# BleAx_nRF52832.net
KiCad netlist of a schematic drawn in EAGLE
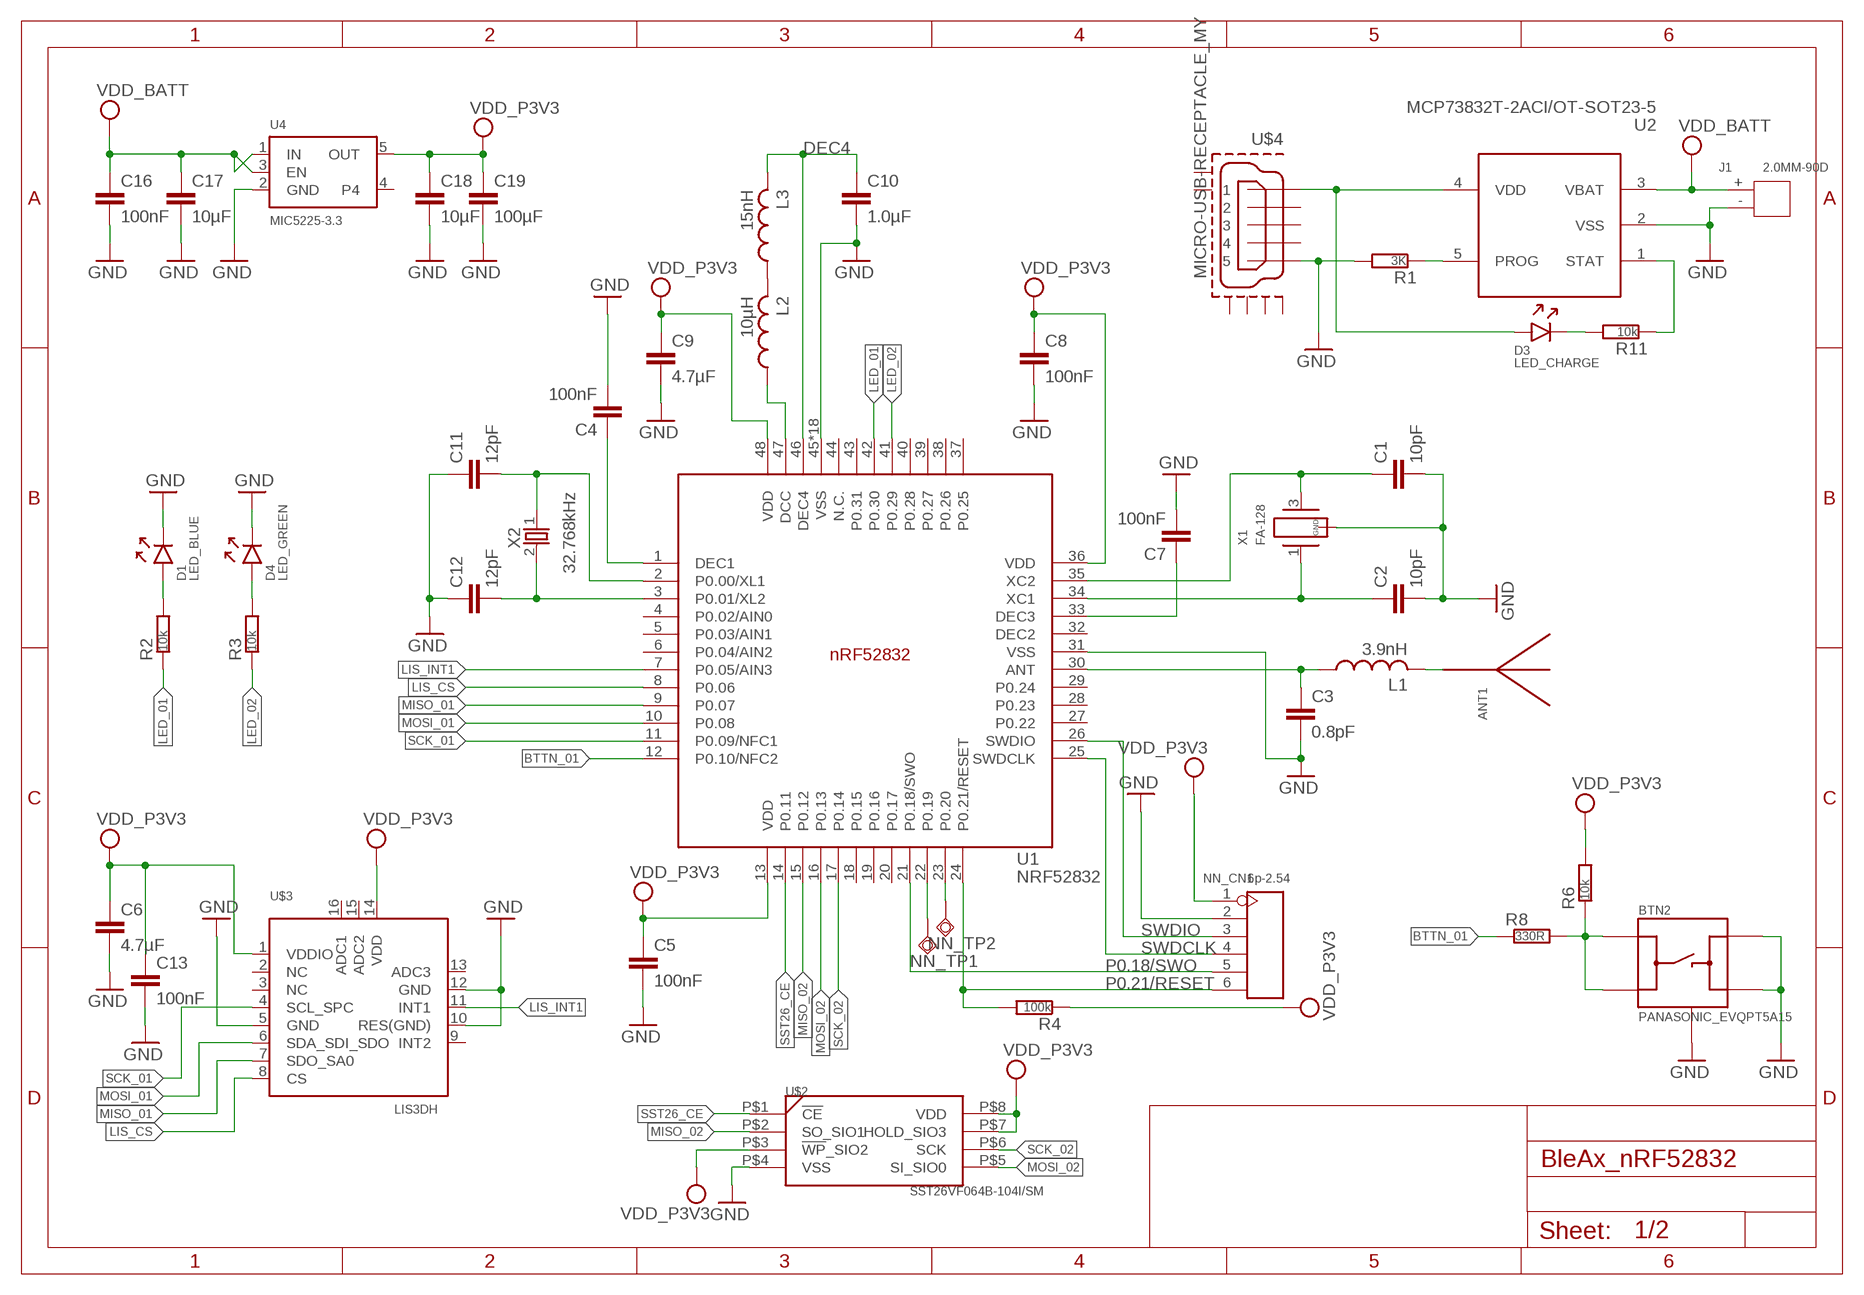
[diagram p0: schematic, sheet 1]
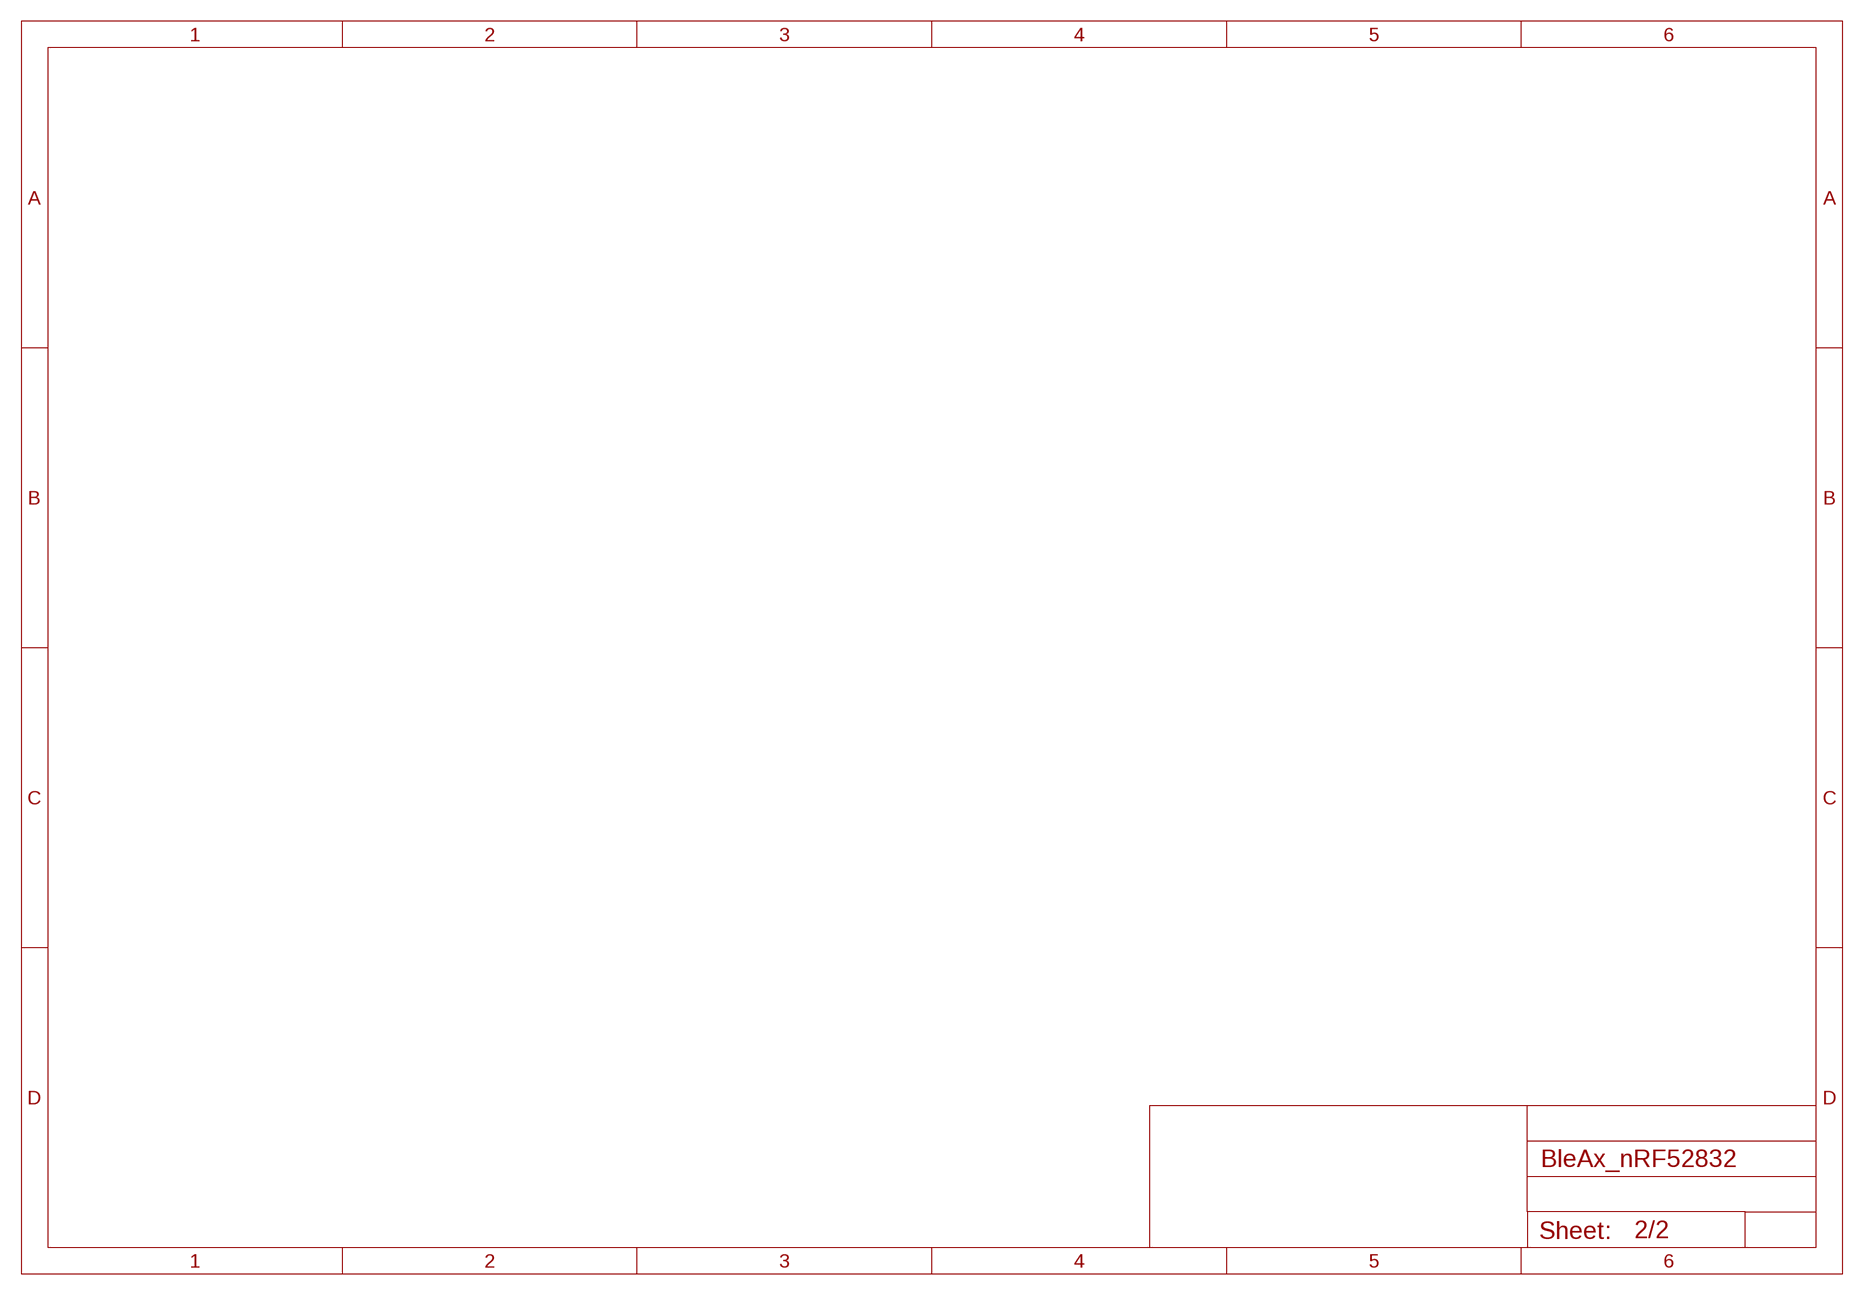
[diagram p1: schematic, sheet 2]

(export (version "E")
  (design (tool "Eeschema 10.0.6"))
  (components
    (comp (ref "ANT1")
      (value "ANTENNA_QUARTER-WAVE_MONOPOLE_MEANDERED_LEFT")
      (footprint "eagle-import:QWMP_MEANDERED_LEFT_+6")
      (libsource (lib "eagle-import") (part "ANTENNA_QUARTER-WAVE_MONOPOLE_MEANDERED_LEFT"))
    )
    (comp (ref "BTN2")
      (value "PANASONIC_EVQPT5A15")
      (footprint "eagle-import:PANASONIC_EVQPT5A15")
      (libsource (lib "eagle-import") (part "PANASONIC_EVQPT5A15"))
    )
    (comp (ref "C1")
      (value "10pF")
      (footprint "eagle-import:RESC0402_N")
      (libsource (lib "eagle-import") (part "CAPACITOR_0402_N"))
    )
    (comp (ref "C2")
      (value "10pF")
      (footprint "eagle-import:RESC0402_N")
      (libsource (lib "eagle-import") (part "CAPACITOR_0402_N"))
    )
    (comp (ref "C3")
      (value "0.8pF")
      (footprint "eagle-import:RESC0402_N")
      (libsource (lib "eagle-import") (part "CAPACITOR_0402_N"))
    )
    (comp (ref "C4")
      (value "100nF")
      (footprint "eagle-import:RESC0402_N")
      (libsource (lib "eagle-import") (part "CAPACITOR_0402_N"))
    )
    (comp (ref "C5")
      (value "100nF")
      (footprint "eagle-import:RESC0402_N")
      (libsource (lib "eagle-import") (part "CAPACITOR_0402_N"))
    )
    (comp (ref "C6")
      (value "4.7µF")
      (footprint "eagle-import:RESC0603_N")
      (libsource (lib "eagle-import") (part "CAPACITOR_0603_N"))
    )
    (comp (ref "C7")
      (value "100nF")
      (footprint "eagle-import:RESC0402_N")
      (libsource (lib "eagle-import") (part "CAPACITOR_0402_N"))
    )
    (comp (ref "C8")
      (value "100nF")
      (footprint "eagle-import:RESC0402_N")
      (libsource (lib "eagle-import") (part "CAPACITOR_0402_N"))
    )
    (comp (ref "C9")
      (value "4.7µF")
      (footprint "eagle-import:RESC0603_N")
      (libsource (lib "eagle-import") (part "CAPACITOR_0603_N"))
    )
    (comp (ref "C10")
      (value "1.0µF")
      (footprint "eagle-import:RESC0603_N")
      (libsource (lib "eagle-import") (part "CAPACITOR_0603_N"))
    )
    (comp (ref "C11")
      (value "12pF")
      (footprint "eagle-import:RESC0402_N")
      (libsource (lib "eagle-import") (part "CAPACITOR_0402_N"))
    )
    (comp (ref "C12")
      (value "12pF")
      (footprint "eagle-import:RESC0402_N")
      (libsource (lib "eagle-import") (part "CAPACITOR_0402_N"))
    )
    (comp (ref "C13")
      (value "100nF")
      (footprint "eagle-import:RESC0402_N")
      (libsource (lib "eagle-import") (part "CAPACITOR_0402_N"))
    )
    (comp (ref "C16")
      (value "100nF")
      (footprint "eagle-import:RESC0402_N")
      (libsource (lib "eagle-import") (part "CAPACITOR_0402_N"))
    )
    (comp (ref "C17")
      (value "10µF")
      (footprint "eagle-import:RESC0603_N")
      (libsource (lib "eagle-import") (part "CAPACITOR_0603_N"))
    )
    (comp (ref "C18")
      (value "10µF")
      (footprint "eagle-import:RESC0603_N")
      (libsource (lib "eagle-import") (part "CAPACITOR_0603_N"))
    )
    (comp (ref "C19")
      (value "100µF")
      (footprint "eagle-import:RESC0805_N")
      (libsource (lib "eagle-import") (part "CAPACITOR_0805_N"))
    )
    (comp (ref "D1")
      (value "LED_BLUE")
      (footprint "eagle-import:DIOC0603_N")
      (libsource (lib "eagle-import") (part "LED"))
    )
    (comp (ref "D3")
      (value "LED_CHARGE")
      (footprint "eagle-import:DIOC0603_N")
      (libsource (lib "eagle-import") (part "LED"))
    )
    (comp (ref "D4")
      (value "LED_GREEN")
      (footprint "eagle-import:DIOC0603_N")
      (libsource (lib "eagle-import") (part "LED"))
    )
    (comp (ref "J1")
      (value "2.0MM-90D")
      (footprint "eagle-import:H2-2.0-90D")
      (libsource (lib "eagle-import") (part "CONN-HEADER-PH-SIDE-(2P-2.0MM)'90D'"))
    )
    (comp (ref "L1")
      (value "3.9nH")
      (footprint "eagle-import:RESC0402_N")
      (libsource (lib "eagle-import") (part "INDUCTOR_0402_N"))
    )
    (comp (ref "L2")
      (value "10µH")
      (footprint "eagle-import:RESC0603_N")
      (libsource (lib "eagle-import") (part "INDUCTOR_0603_N"))
    )
    (comp (ref "L3")
      (value "15nH")
      (footprint "eagle-import:RESC0402_N")
      (libsource (lib "eagle-import") (part "INDUCTOR_0402_N"))
    )
    (comp (ref "NN_CN1")
      (value "6p-2.54")
      (footprint "eagle-import:H6-2.54")
      (fields (field (name "MPN") "F185-1106A1BSYC1"))
      (libsource (lib "eagle-import") (part "DIP-BLACK-FEMALE-HEADER-VERT(6P-2.54)"))
    )
    (comp (ref "NN_TP1")
      (value "TPSQTP08R")
      (footprint "eagle-import:TP08R")
      (libsource (lib "eagle-import") (part "TPSQTP08R"))
    )
    (comp (ref "NN_TP2")
      (value "TPSQTP08R")
      (footprint "eagle-import:TP08R")
      (libsource (lib "eagle-import") (part "TPSQTP08R"))
    )
    (comp (ref "R1")
      (value "3K")
      (footprint "eagle-import:RESC0402_N")
      (libsource (lib "eagle-import") (part "RESISTOR_0402_N"))
    )
    (comp (ref "R2")
      (value "10k")
      (footprint "eagle-import:RESC0402_N")
      (libsource (lib "eagle-import") (part "RESISTOR_0402_N"))
    )
    (comp (ref "R3")
      (value "10k")
      (footprint "eagle-import:RESC0402_N")
      (libsource (lib "eagle-import") (part "RESISTOR_0402_N"))
    )
    (comp (ref "R4")
      (value "100k")
      (footprint "eagle-import:RESC0402_N")
      (libsource (lib "eagle-import") (part "RESISTOR_0402_N"))
    )
    (comp (ref "R6")
      (value "10k")
      (footprint "eagle-import:RESC0402_N")
      (libsource (lib "eagle-import") (part "RESISTOR_0402_N"))
    )
    (comp (ref "R8")
      (value "330R")
      (footprint "eagle-import:RESC0402_N")
      (libsource (lib "eagle-import") (part "RESISTOR_0402_N"))
    )
    (comp (ref "R11")
      (value "10k")
      (footprint "eagle-import:RESC0402_N")
      (libsource (lib "eagle-import") (part "RESISTOR_0402_N"))
    )
    (comp (ref "U$2")
      (value "SST26VF064B-104I/SM")
      (footprint "eagle-import:SOIJ8")
      (libsource (lib "eagle-import") (part "SST26VF"))
    )
    (comp (ref "U$3")
      (value "LIS3DH")
      (footprint "eagle-import:LGA16_3X3MM")
      (libsource (lib "eagle-import") (part "ACCEL_LIS3DHTR"))
    )
    (comp (ref "U$4")
      (value "MICRO-USB-RECEPTACLE_MY")
      (footprint "eagle-import:47589-0001_MY")
      (libsource (lib "eagle-import") (part "MICRO-USB-RECEPTACLE_MY"))
    )
    (comp (ref "U1")
      (value "NRF52832")
      (footprint "eagle-import:QFN40P600X600X90-48_N")
      (libsource (lib "eagle-import") (part "NRF52832"))
    )
    (comp (ref "U2")
      (value "MCP73832T-2ACI/OT-SOT23-5")
      (footprint "eagle-import:SOT-23-5")
      (fields (field (name "MPN") "MCP73832T-2ACI/OT"))
      (libsource (lib "eagle-import") (part "PMIC-MCP73832T-2ACI/OT(SOT23-5)"))
    )
    (comp (ref "U4")
      (value "MIC5225-3.3")
      (footprint "eagle-import:SOT23-5")
      (libsource (lib "eagle-import") (part "VREG_SOT23-5"))
    )
    (comp (ref "X1")
      (value "FA-128")
      (footprint "eagle-import:FA-128")
      (libsource (lib "eagle-import") (part "FA-128"))
    )
    (comp (ref "X2")
      (value "32.768kHz")
      (footprint "eagle-import:XTAL_3215_N")
      (libsource (lib "eagle-import") (part "XTAL_32KHZ"))
    )
  )
  (nets
    (net (code "1") (name "BTTN_01") (class "Default")
      (node (ref "R8") (pin "1") (pinfunction "1_1") (pintype "passive"))
      (node (ref "U1") (pin "12") (pinfunction "P0.10/NFC2_12") (pintype "bidirectional"))
    )
    (net (code "2") (name "DEC4") (class "Default")
      (node (ref "C10") (pin "1") (pinfunction "1_1") (pintype "passive"))
      (node (ref "L3") (pin "2") (pinfunction "2_2") (pintype "passive"))
      (node (ref "U1") (pin "46") (pinfunction "DEC4_46") (pintype "power_in"))
    )
    (net (code "3") (name "GND") (class "Default")
      (node (ref "BTN2") (pin "3") (pinfunction "B_3") (pintype "bidirectional"))
      (node (ref "BTN2") (pin "4") (pinfunction "B'_4") (pintype "bidirectional"))
      (node (ref "BTN2") (pin "5") (pinfunction "GND_5") (pintype "bidirectional"))
      (node (ref "BTN2") (pin "6") (pinfunction "GND_6") (pintype "bidirectional"))
      (node (ref "C1") (pin "2") (pinfunction "2_2") (pintype "passive"))
      (node (ref "C10") (pin "2") (pinfunction "2_2") (pintype "passive"))
      (node (ref "C11") (pin "1") (pinfunction "1_1") (pintype "passive"))
      (node (ref "C12") (pin "1") (pinfunction "1_1") (pintype "passive"))
      (node (ref "C13") (pin "2") (pinfunction "2_2") (pintype "passive"))
      (node (ref "C16") (pin "2") (pinfunction "2_2") (pintype "passive"))
      (node (ref "C17") (pin "2") (pinfunction "2_2") (pintype "passive"))
      (node (ref "C18") (pin "2") (pinfunction "2_2") (pintype "passive"))
      (node (ref "C19") (pin "2") (pinfunction "2_2") (pintype "passive"))
      (node (ref "C2") (pin "2") (pinfunction "2_2") (pintype "passive"))
      (node (ref "C3") (pin "2") (pinfunction "2_2") (pintype "passive"))
      (node (ref "C4") (pin "2") (pinfunction "2_2") (pintype "passive"))
      (node (ref "C5") (pin "2") (pinfunction "2_2") (pintype "passive"))
      (node (ref "C6") (pin "2") (pinfunction "2_2") (pintype "passive"))
      (node (ref "C7") (pin "2") (pinfunction "2_2") (pintype "passive"))
      (node (ref "C8") (pin "2") (pinfunction "2_2") (pintype "passive"))
      (node (ref "C9") (pin "2") (pinfunction "2_2") (pintype "passive"))
      (node (ref "D1") (pin "1") (pinfunction "C_1") (pintype "bidirectional"))
      (node (ref "D4") (pin "1") (pinfunction "C_1") (pintype "bidirectional"))
      (node (ref "J1") (pin "-") (pinfunction "P$2_-") (pintype "bidirectional"))
      (node (ref "NN_CN1") (pin "2") (pinfunction "2_2") (pintype "bidirectional"))
      (node (ref "R1") (pin "2") (pinfunction "2_2") (pintype "passive"))
      (node (ref "U$2") (pin "P$4") (pinfunction "VSS_P$4") (pintype "bidirectional"))
      (node (ref "U$3") (pin "10") (pinfunction "RES(GND)_10") (pintype "bidirectional"))
      (node (ref "U$3") (pin "12") (pinfunction "GND_12") (pintype "power_in"))
      (node (ref "U$3") (pin "5") (pinfunction "GND_5") (pintype "power_in"))
      (node (ref "U$4") (pin "5") (pinfunction "5_5") (pintype "input"))
      (node (ref "U1") (pin "31") (pinfunction "VSS_31") (pintype "bidirectional"))
      (node (ref "U1") (pin "45") (pinfunction "VSS_45") (pintype "power_in"))
      (node (ref "U1") (pin "PAD") (pinfunction "VSS_PAD") (pintype "power_in"))
      (node (ref "U1") (pin "PAD@VIA01") (pinfunction "VSS_PAD@VIA01") (pintype "power_in"))
      (node (ref "U1") (pin "PAD@VIA02") (pinfunction "VSS_PAD@VIA02") (pintype "power_in"))
      (node (ref "U1") (pin "PAD@VIA03") (pinfunction "VSS_PAD@VIA03") (pintype "power_in"))
      (node (ref "U1") (pin "PAD@VIA04") (pinfunction "VSS_PAD@VIA04") (pintype "power_in"))
      (node (ref "U1") (pin "PAD@VIA05") (pinfunction "VSS_PAD@VIA05") (pintype "power_in"))
      (node (ref "U1") (pin "PAD@VIA06") (pinfunction "VSS_PAD@VIA06") (pintype "power_in"))
      (node (ref "U1") (pin "PAD@VIA07") (pinfunction "VSS_PAD@VIA07") (pintype "power_in"))
      (node (ref "U1") (pin "PAD@VIA08") (pinfunction "VSS_PAD@VIA08") (pintype "power_in"))
      (node (ref "U1") (pin "PAD@VIA09") (pinfunction "VSS_PAD@VIA09") (pintype "power_in"))
      (node (ref "U1") (pin "PAD@VIA10") (pinfunction "VSS_PAD@VIA10") (pintype "power_in"))
      (node (ref "U1") (pin "PAD@VIA11") (pinfunction "VSS_PAD@VIA11") (pintype "power_in"))
      (node (ref "U1") (pin "PAD@VIA12") (pinfunction "VSS_PAD@VIA12") (pintype "power_in"))
      (node (ref "U1") (pin "PAD@VIA13") (pinfunction "VSS_PAD@VIA13") (pintype "power_in"))
      (node (ref "U1") (pin "PAD@VIA14") (pinfunction "VSS_PAD@VIA14") (pintype "power_in"))
      (node (ref "U1") (pin "PAD@VIA15") (pinfunction "VSS_PAD@VIA15") (pintype "power_in"))
      (node (ref "U1") (pin "PAD@VIA16") (pinfunction "VSS_PAD@VIA16") (pintype "power_in"))
      (node (ref "U2") (pin "2") (pinfunction "VSS_2") (pintype "passive"))
      (node (ref "U4") (pin "2") (pinfunction "GND_2") (pintype "bidirectional"))
      (node (ref "X1") (pin "2") (pinfunction "GND_2") (pintype "bidirectional"))
      (node (ref "X1") (pin "4") (pinfunction "GND_4") (pintype "bidirectional"))
    )
    (net (code "4") (name "LED_01") (class "Default")
      (node (ref "R2") (pin "1") (pinfunction "1_1") (pintype "passive"))
      (node (ref "U1") (pin "42") (pinfunction "P0.30_42") (pintype "bidirectional"))
    )
    (net (code "5") (name "LED_02") (class "Default")
      (node (ref "R3") (pin "1") (pinfunction "1_1") (pintype "passive"))
      (node (ref "U1") (pin "41") (pinfunction "P0.29_41") (pintype "bidirectional"))
    )
    (net (code "6") (name "LIS_CS") (class "Default")
      (node (ref "U$3") (pin "8") (pinfunction "CS_8") (pintype "input"))
      (node (ref "U1") (pin "8") (pinfunction "P0.06_8") (pintype "bidirectional"))
    )
    (net (code "7") (name "LIS_INT1") (class "Default")
      (node (ref "U$3") (pin "11") (pinfunction "INT1_11") (pintype "output"))
      (node (ref "U1") (pin "7") (pinfunction "P0.05/AIN3_7") (pintype "bidirectional"))
    )
    (net (code "8") (name "MISO_01") (class "Default")
      (node (ref "U$3") (pin "7") (pinfunction "SDO_SA0_7") (pintype "bidirectional"))
      (node (ref "U1") (pin "9") (pinfunction "P0.07_9") (pintype "bidirectional"))
    )
    (net (code "9") (name "MISO_02") (class "Default")
      (node (ref "U$2") (pin "P$2") (pinfunction "SO_SIO1_P$2") (pintype "bidirectional"))
      (node (ref "U1") (pin "15") (pinfunction "P0.12_15") (pintype "bidirectional"))
    )
    (net (code "10") (name "MOSI_01") (class "Default")
      (node (ref "U$3") (pin "6") (pinfunction "SDA_SDI_SDO_6") (pintype "bidirectional"))
      (node (ref "U1") (pin "10") (pinfunction "P0.08_10") (pintype "bidirectional"))
    )
    (net (code "11") (name "MOSI_02") (class "Default")
      (node (ref "U$2") (pin "P$5") (pinfunction "SI_SIO0_P$5") (pintype "bidirectional"))
      (node (ref "U1") (pin "16") (pinfunction "P0.13_16") (pintype "bidirectional"))
    )
    (net (code "12") (name "Net-(ANT1-PadP$1)") (class "Default")
      (node (ref "ANT1") (pin "P$1") (pinfunction "P$1_P$1") (pintype "bidirectional"))
      (node (ref "L1") (pin "2") (pinfunction "2_2") (pintype "passive"))
    )
    (net (code "13") (name "Net-(BTN2-A')") (class "Default")
      (node (ref "BTN2") (pin "1") (pinfunction "A_1") (pintype "bidirectional"))
      (node (ref "BTN2") (pin "2") (pinfunction "A'_2") (pintype "bidirectional"))
      (node (ref "R6") (pin "1") (pinfunction "1_1") (pintype "passive"))
      (node (ref "R8") (pin "2") (pinfunction "2_2") (pintype "passive"))
    )
    (net (code "14") (name "Net-(D1-A)") (class "Default")
      (node (ref "D1") (pin "2") (pinfunction "A_2") (pintype "bidirectional"))
      (node (ref "R2") (pin "2") (pinfunction "2_2") (pintype "passive"))
    )
    (net (code "15") (name "Net-(D3-A)") (class "Default")
      (node (ref "D3") (pin "2") (pinfunction "A_2") (pintype "bidirectional"))
      (node (ref "U$4") (pin "1") (pinfunction "1_1") (pintype "input"))
      (node (ref "U2") (pin "4") (pinfunction "VDD_4") (pintype "input"))
    )
    (net (code "16") (name "Net-(D3-C)") (class "Default")
      (node (ref "D3") (pin "1") (pinfunction "C_1") (pintype "bidirectional"))
      (node (ref "R11") (pin "2") (pinfunction "2_2") (pintype "passive"))
    )
    (net (code "17") (name "Net-(D4-A)") (class "Default")
      (node (ref "D4") (pin "2") (pinfunction "A_2") (pintype "bidirectional"))
      (node (ref "R3") (pin "2") (pinfunction "2_2") (pintype "passive"))
    )
    (net (code "18") (name "Net-(L2-Pad2)") (class "Default")
      (node (ref "L2") (pin "2") (pinfunction "2_2") (pintype "passive"))
      (node (ref "L3") (pin "1") (pinfunction "1_1") (pintype "passive"))
    )
    (net (code "19") (name "Net-(U1-ANT)") (class "Default")
      (node (ref "C3") (pin "1") (pinfunction "1_1") (pintype "passive"))
      (node (ref "L1") (pin "1") (pinfunction "1_1") (pintype "passive"))
      (node (ref "U1") (pin "30") (pinfunction "ANT_30") (pintype "bidirectional"))
    )
    (net (code "20") (name "Net-(U1-DCC)") (class "Default")
      (node (ref "L2") (pin "1") (pinfunction "1_1") (pintype "passive"))
      (node (ref "U1") (pin "47") (pinfunction "DCC_47") (pintype "output"))
    )
    (net (code "21") (name "Net-(U1-DEC1)") (class "Default")
      (node (ref "C4") (pin "1") (pinfunction "1_1") (pintype "passive"))
      (node (ref "U1") (pin "1") (pinfunction "DEC1_1") (pintype "power_in"))
    )
    (net (code "22") (name "Net-(U1-DEC3)") (class "Default")
      (node (ref "C7") (pin "1") (pinfunction "1_1") (pintype "passive"))
      (node (ref "U1") (pin "33") (pinfunction "DEC3_33") (pintype "bidirectional"))
    )
    (net (code "23") (name "Net-(U1-P0.00{slash}XL1)") (class "Default")
      (node (ref "C11") (pin "2") (pinfunction "2_2") (pintype "passive"))
      (node (ref "U1") (pin "2") (pinfunction "P0.00/XL1_2") (pintype "bidirectional"))
      (node (ref "X2") (pin "1") (pinfunction "1_1") (pintype "passive"))
    )
    (net (code "24") (name "Net-(U1-P0.01{slash}XL2)") (class "Default")
      (node (ref "C12") (pin "2") (pinfunction "2_2") (pintype "passive"))
      (node (ref "U1") (pin "3") (pinfunction "P0.01/XL2_3") (pintype "bidirectional"))
      (node (ref "X2") (pin "2") (pinfunction "2_2") (pintype "passive"))
    )
    (net (code "25") (name "Net-(U1-P0.19)") (class "Default")
      (node (ref "NN_TP1") (pin "TP") (pinfunction "TP_TP") (pintype "input"))
      (node (ref "U1") (pin "22") (pinfunction "P0.19_22") (pintype "bidirectional"))
    )
    (net (code "26") (name "Net-(U1-P0.20)") (class "Default")
      (node (ref "NN_TP2") (pin "TP") (pinfunction "TP_TP") (pintype "input"))
      (node (ref "U1") (pin "23") (pinfunction "P0.20_23") (pintype "bidirectional"))
    )
    (net (code "27") (name "Net-(U1-XC1)") (class "Default")
      (node (ref "C2") (pin "1") (pinfunction "1_1") (pintype "passive"))
      (node (ref "U1") (pin "34") (pinfunction "XC1_34") (pintype "input"))
      (node (ref "X1") (pin "1") (pinfunction "1_1") (pintype "bidirectional"))
    )
    (net (code "28") (name "Net-(U1-XC2)") (class "Default")
      (node (ref "C1") (pin "1") (pinfunction "1_1") (pintype "passive"))
      (node (ref "U1") (pin "35") (pinfunction "XC2_35") (pintype "output"))
      (node (ref "X1") (pin "3") (pinfunction "2_3") (pintype "bidirectional"))
    )
    (net (code "29") (name "Net-(U2-PROG)") (class "Default")
      (node (ref "R1") (pin "1") (pinfunction "1_1") (pintype "passive"))
      (node (ref "U2") (pin "5") (pinfunction "PROG_5") (pintype "input"))
    )
    (net (code "30") (name "Net-(U2-STAT)") (class "Default")
      (node (ref "R11") (pin "1") (pinfunction "1_1") (pintype "passive"))
      (node (ref "U2") (pin "1") (pinfunction "STAT_1") (pintype "output"))
    )
    (net (code "31") (name "P0.18{slash}SWO") (class "Default")
      (node (ref "NN_CN1") (pin "5") (pinfunction "5_5") (pintype "bidirectional"))
      (node (ref "U1") (pin "21") (pinfunction "P0.18/SWO_21") (pintype "bidirectional"))
    )
    (net (code "32") (name "P0.21{slash}RESET") (class "Default")
      (node (ref "NN_CN1") (pin "6") (pinfunction "6_6") (pintype "bidirectional"))
      (node (ref "R4") (pin "2") (pinfunction "2_2") (pintype "passive"))
      (node (ref "U1") (pin "24") (pinfunction "P0.21/RESET_24") (pintype "bidirectional"))
    )
    (net (code "33") (name "SCK_01") (class "Default")
      (node (ref "U$3") (pin "4") (pinfunction "SCL_SPC_4") (pintype "bidirectional"))
      (node (ref "U1") (pin "11") (pinfunction "P0.09/NFC1_11") (pintype "bidirectional"))
    )
    (net (code "34") (name "SCK_02") (class "Default")
      (node (ref "U$2") (pin "P$6") (pinfunction "SCK_P$6") (pintype "bidirectional"))
      (node (ref "U1") (pin "17") (pinfunction "P0.14_17") (pintype "bidirectional"))
    )
    (net (code "35") (name "SST26_CE") (class "Default")
      (node (ref "U$2") (pin "P$1") (pinfunction "~{CE}_P$1") (pintype "bidirectional"))
      (node (ref "U1") (pin "14") (pinfunction "P0.11_14") (pintype "bidirectional"))
    )
    (net (code "36") (name "SWDCLK") (class "Default")
      (node (ref "NN_CN1") (pin "4") (pinfunction "4_4") (pintype "bidirectional"))
      (node (ref "U1") (pin "25") (pinfunction "SWDCLK_25") (pintype "input"))
    )
    (net (code "37") (name "SWDIO") (class "Default")
      (node (ref "NN_CN1") (pin "3") (pinfunction "3_3") (pintype "bidirectional"))
      (node (ref "U1") (pin "26") (pinfunction "SWDIO_26") (pintype "bidirectional"))
    )
    (net (code "38") (name "VDD_BATT") (class "Default")
      (node (ref "C16") (pin "1") (pinfunction "1_1") (pintype "passive"))
      (node (ref "C17") (pin "1") (pinfunction "1_1") (pintype "passive"))
      (node (ref "J1") (pin "+") (pinfunction "P$1_+") (pintype "bidirectional"))
      (node (ref "U2") (pin "3") (pinfunction "VBAT_3") (pintype "output"))
      (node (ref "U4") (pin "1") (pinfunction "IN_1") (pintype "bidirectional"))
      (node (ref "U4") (pin "3") (pinfunction "EN_3") (pintype "bidirectional"))
    )
    (net (code "39") (name "VDD_P3V3") (class "Default")
      (node (ref "C13") (pin "1") (pinfunction "1_1") (pintype "passive"))
      (node (ref "C18") (pin "1") (pinfunction "1_1") (pintype "passive"))
      (node (ref "C19") (pin "1") (pinfunction "1_1") (pintype "passive"))
      (node (ref "C5") (pin "1") (pinfunction "1_1") (pintype "passive"))
      (node (ref "C6") (pin "1") (pinfunction "1_1") (pintype "passive"))
      (node (ref "C8") (pin "1") (pinfunction "1_1") (pintype "passive"))
      (node (ref "C9") (pin "1") (pinfunction "1_1") (pintype "passive"))
      (node (ref "NN_CN1") (pin "1") (pinfunction "1_1") (pintype "bidirectional"))
      (node (ref "R4") (pin "1") (pinfunction "1_1") (pintype "passive"))
      (node (ref "R6") (pin "2") (pinfunction "2_2") (pintype "passive"))
      (node (ref "U$2") (pin "P$3") (pinfunction "~{WP}_SIO2_P$3") (pintype "bidirectional"))
      (node (ref "U$2") (pin "P$7") (pinfunction "HOLD_SIO3_P$7") (pintype "bidirectional"))
      (node (ref "U$2") (pin "P$8") (pinfunction "VDD_P$8") (pintype "bidirectional"))
      (node (ref "U$3") (pin "1") (pinfunction "VDDIO_1") (pintype "power_in"))
      (node (ref "U$3") (pin "14") (pinfunction "VDD_14") (pintype "power_in"))
      (node (ref "U1") (pin "13") (pinfunction "VDD_13") (pintype "power_in"))
      (node (ref "U1") (pin "36") (pinfunction "VDD_36") (pintype "power_in"))
      (node (ref "U1") (pin "48") (pinfunction "VDD_48") (pintype "power_in"))
      (node (ref "U4") (pin "5") (pinfunction "OUT_5") (pintype "bidirectional"))
    )
    (net (code "40") (name "unconnected-(U$3-ADC1-Pad16)") (class "Default")
      (node (ref "U$3") (pin "16") (pinfunction "ADC1_16") (pintype "input"))
    )
    (net (code "41") (name "unconnected-(U$3-ADC2-Pad15)") (class "Default")
      (node (ref "U$3") (pin "15") (pinfunction "ADC2_15") (pintype "input"))
    )
    (net (code "42") (name "unconnected-(U$3-ADC3-Pad13)") (class "Default")
      (node (ref "U$3") (pin "13") (pinfunction "ADC3_13") (pintype "input"))
    )
    (net (code "43") (name "unconnected-(U$3-INT2-Pad9)") (class "Default")
      (node (ref "U$3") (pin "9") (pinfunction "INT2_9") (pintype "output"))
    )
    (net (code "44") (name "unconnected-(U$3-NC-Pad2)") (class "Default")
      (node (ref "U$3") (pin "2") (pinfunction "NC_2") (pintype "no_connect"))
    )
    (net (code "45") (name "unconnected-(U$3-NC-Pad3)") (class "Default")
      (node (ref "U$3") (pin "3") (pinfunction "NC_3") (pintype "no_connect"))
    )
    (net (code "46") (name "unconnected-(U$4-GND1-PadP$1)") (class "Default")
      (node (ref "U$4") (pin "P$1") (pinfunction "GND1_P$1") (pintype "bidirectional"))
    )
    (net (code "47") (name "unconnected-(U$4-GND2-PadP$2)") (class "Default")
      (node (ref "U$4") (pin "P$2") (pinfunction "GND2_P$2") (pintype "bidirectional"))
    )
    (net (code "48") (name "unconnected-(U$4-GND3-PadP$3)") (class "Default")
      (node (ref "U$4") (pin "P$3") (pinfunction "GND3_P$3") (pintype "bidirectional"))
    )
    (net (code "49") (name "unconnected-(U$4-GND4-PadP$4)") (class "Default")
      (node (ref "U$4") (pin "P$4") (pinfunction "GND4_P$4") (pintype "bidirectional"))
    )
    (net (code "50") (name "unconnected-(U$4-GND5-PadP$5)") (class "Default")
      (node (ref "U$4") (pin "P$5") (pinfunction "GND5_P$5") (pintype "bidirectional"))
    )
    (net (code "51") (name "unconnected-(U$4-GND6-PadP$6)") (class "Default")
      (node (ref "U$4") (pin "P$6") (pinfunction "GND6_P$6") (pintype "bidirectional"))
    )
    (net (code "52") (name "unconnected-(U$4-Pad2)") (class "Default")
      (node (ref "U$4") (pin "2") (pinfunction "2_2") (pintype "input"))
    )
    (net (code "53") (name "unconnected-(U$4-Pad3)") (class "Default")
      (node (ref "U$4") (pin "3") (pinfunction "3_3") (pintype "input"))
    )
    (net (code "54") (name "unconnected-(U$4-Pad4)") (class "Default")
      (node (ref "U$4") (pin "4") (pinfunction "4_4") (pintype "input"))
    )
    (net (code "55") (name "unconnected-(U1-DEC2-Pad32)") (class "Default")
      (node (ref "U1") (pin "32") (pinfunction "DEC2_32") (pintype "bidirectional"))
    )
    (net (code "56") (name "unconnected-(U1-N.C.-Pad44)") (class "Default")
      (node (ref "U1") (pin "44") (pinfunction "N.C._44") (pintype "no_connect"))
    )
    (net (code "57") (name "unconnected-(U1-P0.02{slash}AIN0-Pad4)") (class "Default")
      (node (ref "U1") (pin "4") (pinfunction "P0.02/AIN0_4") (pintype "bidirectional"))
    )
    (net (code "58") (name "unconnected-(U1-P0.03{slash}AIN1-Pad5)") (class "Default")
      (node (ref "U1") (pin "5") (pinfunction "P0.03/AIN1_5") (pintype "bidirectional"))
    )
    (net (code "59") (name "unconnected-(U1-P0.04{slash}AIN2-Pad6)") (class "Default")
      (node (ref "U1") (pin "6") (pinfunction "P0.04/AIN2_6") (pintype "bidirectional"))
    )
    (net (code "60") (name "unconnected-(U1-P0.15-Pad18)") (class "Default")
      (node (ref "U1") (pin "18") (pinfunction "P0.15_18") (pintype "bidirectional"))
    )
    (net (code "61") (name "unconnected-(U1-P0.16-Pad19)") (class "Default")
      (node (ref "U1") (pin "19") (pinfunction "P0.16_19") (pintype "bidirectional"))
    )
    (net (code "62") (name "unconnected-(U1-P0.17-Pad20)") (class "Default")
      (node (ref "U1") (pin "20") (pinfunction "P0.17_20") (pintype "bidirectional"))
    )
    (net (code "63") (name "unconnected-(U1-P0.22-Pad27)") (class "Default")
      (node (ref "U1") (pin "27") (pinfunction "P0.22_27") (pintype "bidirectional"))
    )
    (net (code "64") (name "unconnected-(U1-P0.23-Pad28)") (class "Default")
      (node (ref "U1") (pin "28") (pinfunction "P0.23_28") (pintype "bidirectional"))
    )
    (net (code "65") (name "unconnected-(U1-P0.24-Pad29)") (class "Default")
      (node (ref "U1") (pin "29") (pinfunction "P0.24_29") (pintype "bidirectional"))
    )
    (net (code "66") (name "unconnected-(U1-P0.25-Pad37)") (class "Default")
      (node (ref "U1") (pin "37") (pinfunction "P0.25_37") (pintype "bidirectional"))
    )
    (net (code "67") (name "unconnected-(U1-P0.26-Pad38)") (class "Default")
      (node (ref "U1") (pin "38") (pinfunction "P0.26_38") (pintype "bidirectional"))
    )
    (net (code "68") (name "unconnected-(U1-P0.27-Pad39)") (class "Default")
      (node (ref "U1") (pin "39") (pinfunction "P0.27_39") (pintype "bidirectional"))
    )
    (net (code "69") (name "unconnected-(U1-P0.28-Pad40)") (class "Default")
      (node (ref "U1") (pin "40") (pinfunction "P0.28_40") (pintype "bidirectional"))
    )
    (net (code "70") (name "unconnected-(U1-P0.31-Pad43)") (class "Default")
      (node (ref "U1") (pin "43") (pinfunction "P0.31_43") (pintype "bidirectional"))
    )
    (net (code "71") (name "unconnected-(U4-P4-Pad4)") (class "Default")
      (node (ref "U4") (pin "4") (pinfunction "P4_4") (pintype "bidirectional"))
    )
  )
)
